# BrewPi_Fuscus_Board_RJ-45.net
KiCad netlist of a schematic drawn in EAGLE
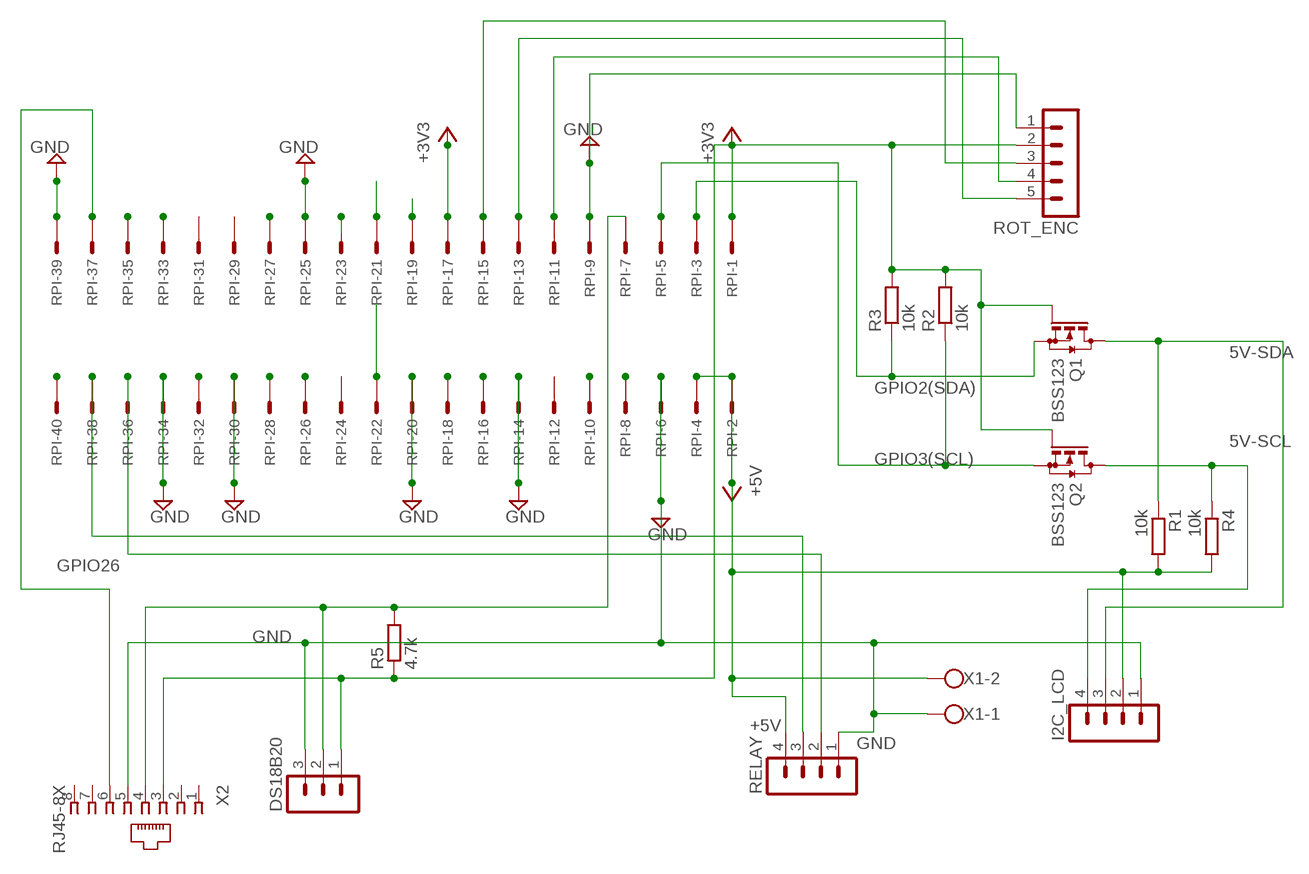
[diagram p0: schematic, sheet 1]

(export (version "E")
  (design (tool "Eeschema 10.0.6"))
  (components
    (comp (ref "DS18B20")
      (value "MA03-1")
      (footprint "eagle-import:MA03-1")
      (libsource (lib "eagle-import") (part "MA03-1"))
    )
    (comp (ref "I2C_LCD")
      (value "MA04-1")
      (footprint "eagle-import:MA04-1")
      (libsource (lib "eagle-import") (part "MA04-1"))
    )
    (comp (ref "Q1")
      (value "BSS123")
      (footprint "eagle-import:SOT23")
      (libsource (lib "eagle-import") (part "BSS123"))
    )
    (comp (ref "Q2")
      (value "BSS123")
      (footprint "eagle-import:SOT23")
      (libsource (lib "eagle-import") (part "BSS123"))
    )
    (comp (ref "R1")
      (value "10k")
      (footprint "eagle-import:M1206")
      (libsource (lib "eagle-import") (part "R-EU_M1206"))
    )
    (comp (ref "R2")
      (value "10k")
      (footprint "eagle-import:M1206")
      (libsource (lib "eagle-import") (part "R-EU_M1206"))
    )
    (comp (ref "R3")
      (value "10k")
      (footprint "eagle-import:M1206")
      (libsource (lib "eagle-import") (part "R-EU_M1206"))
    )
    (comp (ref "R4")
      (value "10k")
      (footprint "eagle-import:M1206")
      (libsource (lib "eagle-import") (part "R-EU_M1206"))
    )
    (comp (ref "R5")
      (value "4.7k")
      (footprint "eagle-import:M1206")
      (libsource (lib "eagle-import") (part "R-EU_M1206"))
    )
    (comp (ref "RELAY")
      (value "MA04-1")
      (footprint "eagle-import:MA04-1")
      (libsource (lib "eagle-import") (part "MA04-1"))
    )
    (comp (ref "ROT_ENC")
      (value "MA05-1")
      (footprint "eagle-import:MA05-1")
      (libsource (lib "eagle-import") (part "MA05-1"))
    )
    (comp (ref "RPI")
      (value "057-040-1")
      (footprint "eagle-import:057-040-1")
      (libsource (lib "eagle-import") (part "057-040-1"))
    )
    (comp (ref "X1")
      (value "W237-102")
      (footprint "eagle-import:W237-102")
      (fields (field (name "MPN") "237-102"))
      (libsource (lib "eagle-import") (part "W237-102"))
    )
    (comp (ref "X2")
      (value "RJ45-8X")
      (footprint "eagle-import:RJ45-NO-SHIELD")
      (libsource (lib "eagle-import") (part "RJ45-8X"))
    )
  )
  (nets
    (net (code "1") (name "+3V3") (class "Default")
      (node (ref "DS18B20") (pin "1") (pinfunction "1_1") (pintype "passive"))
      (node (ref "Q1") (pin "1") (pinfunction "G_1") (pintype "passive"))
      (node (ref "Q2") (pin "1") (pinfunction "G_1") (pintype "passive"))
      (node (ref "R2") (pin "2") (pinfunction "2_2") (pintype "passive"))
      (node (ref "R3") (pin "2") (pinfunction "2_2") (pintype "passive"))
      (node (ref "R5") (pin "1") (pinfunction "1_1") (pintype "passive"))
      (node (ref "ROT_ENC") (pin "2") (pinfunction "2_2") (pintype "passive"))
      (node (ref "RPI") (pin "1") (pinfunction "S_1") (pintype "passive"))
      (node (ref "RPI") (pin "17") (pinfunction "S_17") (pintype "passive"))
      (node (ref "X2") (pin "3") (pinfunction "3_3") (pintype "passive"))
    )
    (net (code "2") (name "+5V") (class "Default")
      (node (ref "I2C_LCD") (pin "2") (pinfunction "2_2") (pintype "passive"))
      (node (ref "R1") (pin "2") (pinfunction "2_2") (pintype "passive"))
      (node (ref "R4") (pin "2") (pinfunction "2_2") (pintype "passive"))
      (node (ref "RELAY") (pin "4") (pinfunction "4_4") (pintype "passive"))
      (node (ref "RPI") (pin "2") (pinfunction "S_2") (pintype "passive"))
      (node (ref "RPI") (pin "4") (pinfunction "S_4") (pintype "passive"))
      (node (ref "X1") (pin "2") (pinfunction "KL_2") (pintype "passive"))
    )
    (net (code "3") (name "/5V-SCL") (class "Default")
      (node (ref "I2C_LCD") (pin "4") (pinfunction "4_4") (pintype "passive"))
      (node (ref "Q2") (pin "3") (pinfunction "D_3") (pintype "passive"))
      (node (ref "R4") (pin "1") (pinfunction "1_1") (pintype "passive"))
    )
    (net (code "4") (name "/5V-SDA") (class "Default")
      (node (ref "I2C_LCD") (pin "3") (pinfunction "3_3") (pintype "passive"))
      (node (ref "Q1") (pin "3") (pinfunction "D_3") (pintype "passive"))
      (node (ref "R1") (pin "1") (pinfunction "1_1") (pintype "passive"))
    )
    (net (code "5") (name "/GPIO2(SDA)") (class "Default")
      (node (ref "Q1") (pin "2") (pinfunction "S_2") (pintype "passive"))
      (node (ref "R3") (pin "1") (pinfunction "1_1") (pintype "passive"))
      (node (ref "RPI") (pin "3") (pinfunction "S_3") (pintype "passive"))
    )
    (net (code "6") (name "/GPIO3(SCL)") (class "Default")
      (node (ref "Q2") (pin "2") (pinfunction "S_2") (pintype "passive"))
      (node (ref "R2") (pin "1") (pinfunction "1_1") (pintype "passive"))
      (node (ref "RPI") (pin "5") (pinfunction "S_5") (pintype "passive"))
    )
    (net (code "7") (name "/GPIO26") (class "Default")
      (node (ref "RPI") (pin "37") (pinfunction "S_37") (pintype "passive"))
      (node (ref "X2") (pin "6") (pinfunction "6_6") (pintype "passive"))
    )
    (net (code "8") (name "GND") (class "Default")
      (node (ref "DS18B20") (pin "3") (pinfunction "3_3") (pintype "passive"))
      (node (ref "I2C_LCD") (pin "1") (pinfunction "1_1") (pintype "passive"))
      (node (ref "RELAY") (pin "1") (pinfunction "1_1") (pintype "passive"))
      (node (ref "ROT_ENC") (pin "1") (pinfunction "1_1") (pintype "passive"))
      (node (ref "RPI") (pin "14") (pinfunction "S_14") (pintype "passive"))
      (node (ref "RPI") (pin "20") (pinfunction "S_20") (pintype "passive"))
      (node (ref "RPI") (pin "25") (pinfunction "S_25") (pintype "passive"))
      (node (ref "RPI") (pin "30") (pinfunction "S_30") (pintype "passive"))
      (node (ref "RPI") (pin "34") (pinfunction "S_34") (pintype "passive"))
      (node (ref "RPI") (pin "39") (pinfunction "S_39") (pintype "passive"))
      (node (ref "RPI") (pin "6") (pinfunction "S_6") (pintype "passive"))
      (node (ref "RPI") (pin "9") (pinfunction "S_9") (pintype "passive"))
      (node (ref "X1") (pin "1") (pinfunction "KL_1") (pintype "passive"))
      (node (ref "X2") (pin "5") (pinfunction "5_5") (pintype "passive"))
    )
    (net (code "9") (name "Net-(RPIAD-S)") (class "Default")
      (node (ref "RELAY") (pin "2") (pinfunction "2_2") (pintype "passive"))
      (node (ref "RPI") (pin "36") (pinfunction "S_36") (pintype "passive"))
    )
    (net (code "10") (name "Net-(RPIAF-S)") (class "Default")
      (node (ref "RELAY") (pin "3") (pinfunction "3_3") (pintype "passive"))
      (node (ref "RPI") (pin "38") (pinfunction "S_38") (pintype "passive"))
    )
    (net (code "11") (name "Net-(RPIAL-S)") (class "Default")
      (node (ref "DS18B20") (pin "2") (pinfunction "2_2") (pintype "passive"))
      (node (ref "R5") (pin "2") (pinfunction "2_2") (pintype "passive"))
      (node (ref "RPI") (pin "7") (pinfunction "S_7") (pintype "passive"))
      (node (ref "X2") (pin "4") (pinfunction "4_4") (pintype "passive"))
    )
    (net (code "12") (name "Net-(RPIC-S)") (class "Default")
      (node (ref "ROT_ENC") (pin "4") (pinfunction "4_4") (pintype "passive"))
      (node (ref "RPI") (pin "11") (pinfunction "S_11") (pintype "passive"))
    )
    (net (code "13") (name "Net-(RPIE-S)") (class "Default")
      (node (ref "ROT_ENC") (pin "5") (pinfunction "5_5") (pintype "passive"))
      (node (ref "RPI") (pin "13") (pinfunction "S_13") (pintype "passive"))
    )
    (net (code "14") (name "Net-(RPIG-S)") (class "Default")
      (node (ref "ROT_ENC") (pin "3") (pinfunction "3_3") (pintype "passive"))
      (node (ref "RPI") (pin "15") (pinfunction "S_15") (pintype "passive"))
    )
    (net (code "15") (name "unconnected-(RPIAA-S-Pad33)") (class "Default")
      (node (ref "RPI") (pin "33") (pinfunction "S_33") (pintype "passive"))
    )
    (net (code "16") (name "unconnected-(RPIAC-S-Pad35)") (class "Default")
      (node (ref "RPI") (pin "35") (pinfunction "S_35") (pintype "passive"))
    )
    (net (code "17") (name "unconnected-(RPIAI-S-Pad40)") (class "Default")
      (node (ref "RPI") (pin "40") (pinfunction "S_40") (pintype "passive"))
    )
    (net (code "18") (name "unconnected-(RPIAM-S-Pad8)") (class "Default")
      (node (ref "RPI") (pin "8") (pinfunction "S_8") (pintype "passive"))
    )
    (net (code "19") (name "unconnected-(RPIB-S-Pad10)") (class "Default")
      (node (ref "RPI") (pin "10") (pinfunction "S_10") (pintype "passive"))
    )
    (net (code "20") (name "unconnected-(RPID-S-Pad12)") (class "Default")
      (node (ref "RPI") (pin "12") (pinfunction "S_12") (pintype "passive"))
    )
    (net (code "21") (name "unconnected-(RPIH-S-Pad16)") (class "Default")
      (node (ref "RPI") (pin "16") (pinfunction "S_16") (pintype "passive"))
    )
    (net (code "22") (name "unconnected-(RPIJ-S-Pad18)") (class "Default")
      (node (ref "RPI") (pin "18") (pinfunction "S_18") (pintype "passive"))
    )
    (net (code "23") (name "unconnected-(RPIK-S-Pad19)") (class "Default")
      (node (ref "RPI") (pin "19") (pinfunction "S_19") (pintype "passive"))
    )
    (net (code "24") (name "unconnected-(RPIN-S-Pad21)") (class "Default")
      (node (ref "RPI") (pin "21") (pinfunction "S_21") (pintype "passive"))
    )
    (net (code "25") (name "unconnected-(RPIO-S-Pad22)") (class "Default")
      (node (ref "RPI") (pin "22") (pinfunction "S_22") (pintype "passive"))
    )
    (net (code "26") (name "unconnected-(RPIP-S-Pad23)") (class "Default")
      (node (ref "RPI") (pin "23") (pinfunction "S_23") (pintype "passive"))
    )
    (net (code "27") (name "unconnected-(RPIQ-S-Pad24)") (class "Default")
      (node (ref "RPI") (pin "24") (pinfunction "S_24") (pintype "passive"))
    )
    (net (code "28") (name "unconnected-(RPIS-S-Pad26)") (class "Default")
      (node (ref "RPI") (pin "26") (pinfunction "S_26") (pintype "passive"))
    )
    (net (code "29") (name "unconnected-(RPIT-S-Pad27)") (class "Default")
      (node (ref "RPI") (pin "27") (pinfunction "S_27") (pintype "passive"))
    )
    (net (code "30") (name "unconnected-(RPIU-S-Pad28)") (class "Default")
      (node (ref "RPI") (pin "28") (pinfunction "S_28") (pintype "passive"))
    )
    (net (code "31") (name "unconnected-(RPIV-S-Pad29)") (class "Default")
      (node (ref "RPI") (pin "29") (pinfunction "S_29") (pintype "passive"))
    )
    (net (code "32") (name "unconnected-(RPIY-S-Pad31)") (class "Default")
      (node (ref "RPI") (pin "31") (pinfunction "S_31") (pintype "passive"))
    )
    (net (code "33") (name "unconnected-(RPIZ-S-Pad32)") (class "Default")
      (node (ref "RPI") (pin "32") (pinfunction "S_32") (pintype "passive"))
    )
    (net (code "34") (name "unconnected-(X2-Pad1)") (class "Default")
      (node (ref "X2") (pin "1") (pinfunction "1_1") (pintype "passive"))
    )
    (net (code "35") (name "unconnected-(X2-Pad2)") (class "Default")
      (node (ref "X2") (pin "2") (pinfunction "2_2") (pintype "passive"))
    )
    (net (code "36") (name "unconnected-(X2-Pad7)") (class "Default")
      (node (ref "X2") (pin "7") (pinfunction "7_7") (pintype "passive"))
    )
    (net (code "37") (name "unconnected-(X2-Pad8)") (class "Default")
      (node (ref "X2") (pin "8") (pinfunction "8_8") (pintype "passive"))
    )
  )
)
